# servoUART_by_Aruduino.net
KiCad netlist of a schematic drawn in EAGLE
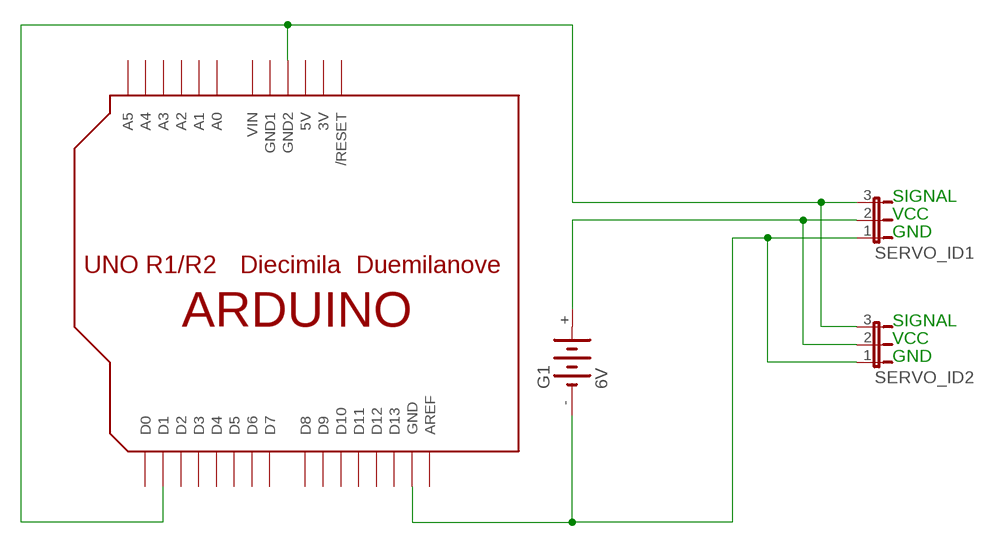
[diagram p0: schematic, sheet 1]

(export (version "E")
  (design (tool "Eeschema 10.0.6"))
  (components
    (comp (ref "G1")
      (value "6V")
      (footprint "eagle-import:3V11R")
      (libsource (lib "eagle-import") (part "3V11R"))
    )
    (comp (ref "SERVO_ID1")
      (value "JP2E")
      (footprint "eagle-import:JP2")
      (libsource (lib "eagle-import") (part "JP2E"))
    )
    (comp (ref "SERVO_ID2")
      (value "JP2E")
      (footprint "eagle-import:JP2")
      (libsource (lib "eagle-import") (part "JP2E"))
    )
    (comp (ref "U$1")
      (value "ARDUINOUNO")
      (footprint "eagle-import:ARDUINO")
      (libsource (lib "eagle-import") (part "ARDUINOUNO"))
    )
  )
  (nets
    (net (code "1") (name "/3V") (class "Default")
      (node (ref "U$1") (pin "3V") (pinfunction "3V_3V") (pintype "power_in"))
    )
    (net (code "2") (name "/5V") (class "Default")
      (node (ref "U$1") (pin "5V") (pinfunction "5V_5V") (pintype "power_in"))
    )
    (net (code "3") (name "/GND1") (class "Default")
      (node (ref "U$1") (pin "GND1") (pinfunction "GND1_GND1") (pintype "power_in"))
    )
    (net (code "4") (name "/VIN") (class "Default")
      (node (ref "U$1") (pin "VIN") (pinfunction "VIN_VIN") (pintype "power_in"))
    )
    (net (code "5") (name "Net-(G1-Pad+)") (class "Default")
      (node (ref "G1") (pin "+") (pinfunction "+_+") (pintype "passive"))
      (node (ref "SERVO_ID1") (pin "2") (pinfunction "2_2") (pintype "passive"))
      (node (ref "SERVO_ID2") (pin "2") (pinfunction "2_2") (pintype "passive"))
    )
    (net (code "6") (name "Net-(G1-Pad-)") (class "Default")
      (node (ref "G1") (pin "-") (pinfunction "-_-") (pintype "passive"))
      (node (ref "SERVO_ID1") (pin "1") (pinfunction "1_1") (pintype "passive"))
      (node (ref "SERVO_ID2") (pin "1") (pinfunction "1_1") (pintype "passive"))
      (node (ref "U$1") (pin "GND") (pinfunction "GND_GND") (pintype "power_in"))
    )
    (net (code "7") (name "Net-(SERVO_ID1-Pad3)") (class "Default")
      (node (ref "SERVO_ID1") (pin "3") (pinfunction "3_3") (pintype "passive"))
      (node (ref "SERVO_ID2") (pin "3") (pinfunction "3_3") (pintype "passive"))
      (node (ref "U$1") (pin "D1") (pinfunction "D1_D1") (pintype "bidirectional"))
      (node (ref "U$1") (pin "GND2") (pinfunction "GND2_GND2") (pintype "power_in"))
    )
    (net (code "8") (name "unconnected-(U$1-PadA0)") (class "Default")
      (node (ref "U$1") (pin "A0") (pinfunction "A0_A0") (pintype "bidirectional"))
    )
    (net (code "9") (name "unconnected-(U$1-PadA1)") (class "Default")
      (node (ref "U$1") (pin "A1") (pinfunction "A1_A1") (pintype "bidirectional"))
    )
    (net (code "10") (name "unconnected-(U$1-PadA2)") (class "Default")
      (node (ref "U$1") (pin "A2") (pinfunction "A2_A2") (pintype "bidirectional"))
    )
    (net (code "11") (name "unconnected-(U$1-PadA3)") (class "Default")
      (node (ref "U$1") (pin "A3") (pinfunction "A3_A3") (pintype "bidirectional"))
    )
    (net (code "12") (name "unconnected-(U$1-PadA4)") (class "Default")
      (node (ref "U$1") (pin "A4") (pinfunction "A4_A4") (pintype "bidirectional"))
    )
    (net (code "13") (name "unconnected-(U$1-PadA5)") (class "Default")
      (node (ref "U$1") (pin "A5") (pinfunction "A5_A5") (pintype "bidirectional"))
    )
    (net (code "14") (name "unconnected-(U$1-PadAREF)") (class "Default")
      (node (ref "U$1") (pin "AREF") (pinfunction "AREF_AREF") (pintype "bidirectional"))
    )
    (net (code "15") (name "unconnected-(U$1-PadD0)") (class "Default")
      (node (ref "U$1") (pin "D0") (pinfunction "D0_D0") (pintype "bidirectional"))
    )
    (net (code "16") (name "unconnected-(U$1-PadD2)") (class "Default")
      (node (ref "U$1") (pin "D2") (pinfunction "D2_D2") (pintype "bidirectional"))
    )
    (net (code "17") (name "unconnected-(U$1-PadD3)") (class "Default")
      (node (ref "U$1") (pin "D3") (pinfunction "D3_D3") (pintype "bidirectional"))
    )
    (net (code "18") (name "unconnected-(U$1-PadD4)") (class "Default")
      (node (ref "U$1") (pin "D4") (pinfunction "D4_D4") (pintype "bidirectional"))
    )
    (net (code "19") (name "unconnected-(U$1-PadD5)") (class "Default")
      (node (ref "U$1") (pin "D5") (pinfunction "D5_D5") (pintype "bidirectional"))
    )
    (net (code "20") (name "unconnected-(U$1-PadD6)") (class "Default")
      (node (ref "U$1") (pin "D6") (pinfunction "D6_D6") (pintype "bidirectional"))
    )
    (net (code "21") (name "unconnected-(U$1-PadD7)") (class "Default")
      (node (ref "U$1") (pin "D7") (pinfunction "D7_D7") (pintype "bidirectional"))
    )
    (net (code "22") (name "unconnected-(U$1-PadD8)") (class "Default")
      (node (ref "U$1") (pin "D8") (pinfunction "D8_D8") (pintype "bidirectional"))
    )
    (net (code "23") (name "unconnected-(U$1-PadD9)") (class "Default")
      (node (ref "U$1") (pin "D9") (pinfunction "D9_D9") (pintype "bidirectional"))
    )
    (net (code "24") (name "unconnected-(U$1-PadD10)") (class "Default")
      (node (ref "U$1") (pin "D10") (pinfunction "D10_D10") (pintype "bidirectional"))
    )
    (net (code "25") (name "unconnected-(U$1-PadD11)") (class "Default")
      (node (ref "U$1") (pin "D11") (pinfunction "D11_D11") (pintype "bidirectional"))
    )
    (net (code "26") (name "unconnected-(U$1-PadD12)") (class "Default")
      (node (ref "U$1") (pin "D12") (pinfunction "D12_D12") (pintype "bidirectional"))
    )
    (net (code "27") (name "unconnected-(U$1-PadD13)") (class "Default")
      (node (ref "U$1") (pin "D13") (pinfunction "D13_D13") (pintype "bidirectional"))
    )
    (net (code "28") (name "unconnected-(U$1-{slash}RESET-PadRESET)") (class "Default")
      (node (ref "U$1") (pin "RESET") (pinfunction "/RESET_RESET") (pintype "bidirectional"))
    )
  )
)
